# Sport_Analyzer_1_0_1.net
KiCad netlist of a schematic drawn in EAGLE
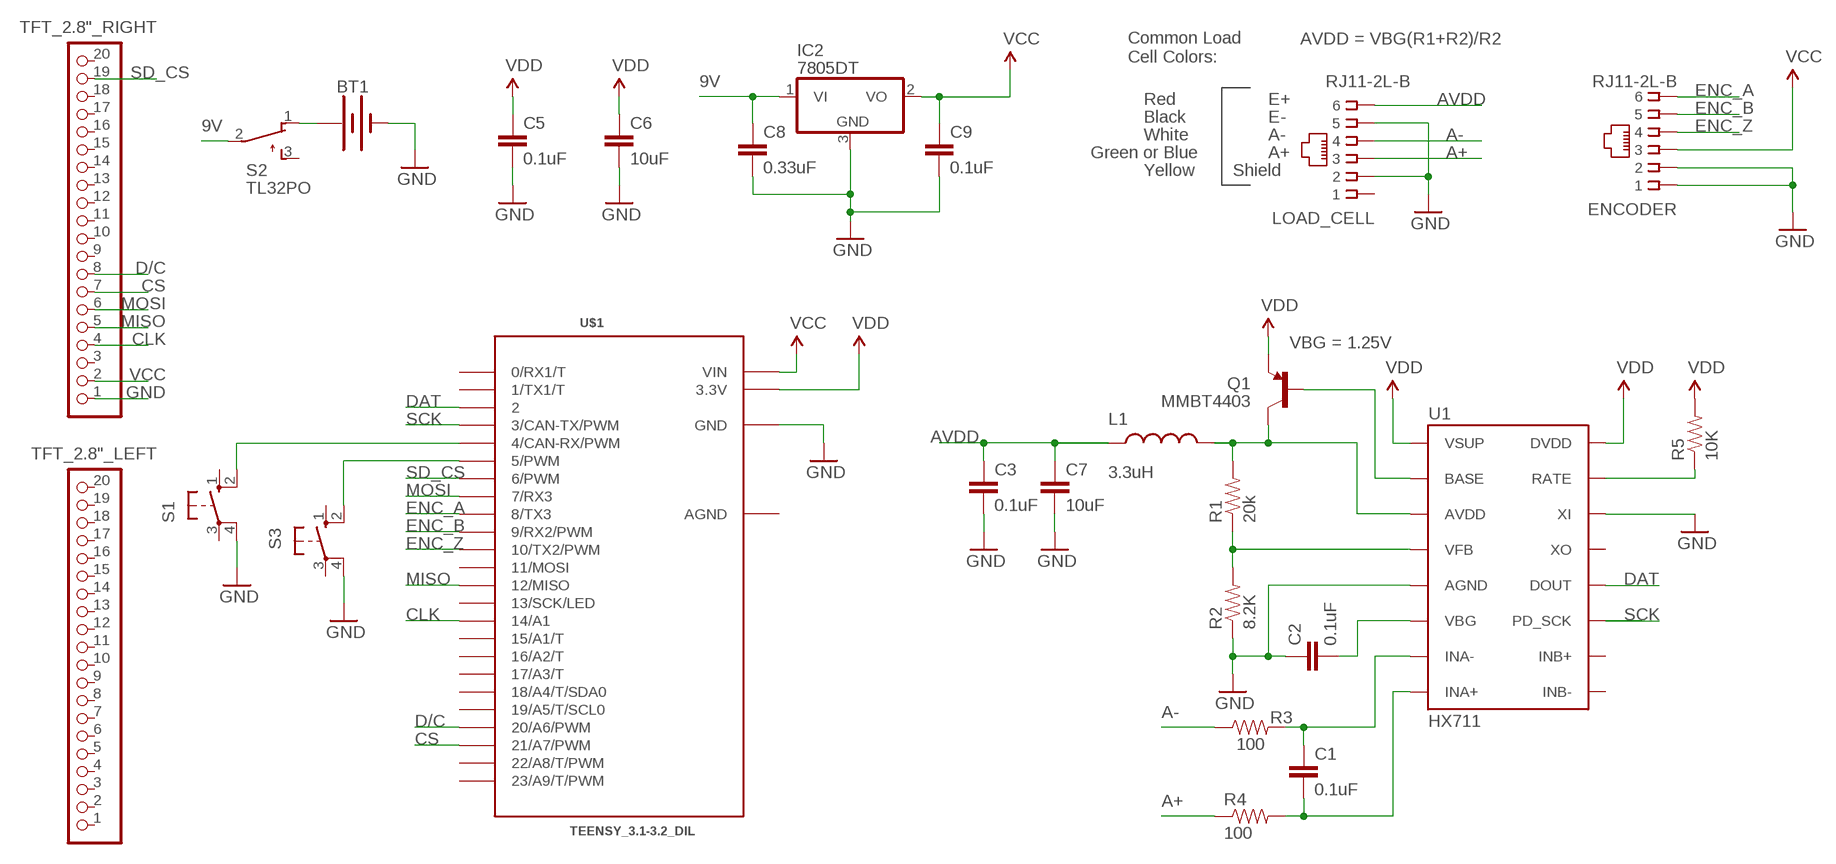
[diagram p0: schematic, sheet 1]

(export (version "E")
  (design (tool "Eeschema 10.0.6"))
  (components
    (comp (ref "BT1")
      (value "BATTERY-9V")
      (footprint "eagle-import:BATTCON_9V")
      (libsource (lib "eagle-import") (part "BATTERY-9V"))
    )
    (comp (ref "C1")
      (value "0.1uF")
      (footprint "eagle-import:0603-CAP")
      (libsource (lib "eagle-import") (part "0.1UF-25V-5%(0603)"))
    )
    (comp (ref "C2")
      (value "0.1uF")
      (footprint "eagle-import:0603-CAP")
      (libsource (lib "eagle-import") (part "0.1UF-25V-5%(0603)"))
    )
    (comp (ref "C3")
      (value "0.1uF")
      (footprint "eagle-import:0603-CAP")
      (libsource (lib "eagle-import") (part "0.1UF-25V-5%(0603)"))
    )
    (comp (ref "C5")
      (value "0.1uF")
      (footprint "eagle-import:0603-CAP")
      (libsource (lib "eagle-import") (part "0.1UF-25V-5%(0603)"))
    )
    (comp (ref "C6")
      (value "10uF")
      (footprint "eagle-import:1210")
      (libsource (lib "eagle-import") (part "10UF50V20%(1210)"))
    )
    (comp (ref "C7")
      (value "10uF")
      (footprint "eagle-import:1210")
      (libsource (lib "eagle-import") (part "10UF50V20%(1210)"))
    )
    (comp (ref "C8")
      (value "0.33uF")
      (footprint "eagle-import:0603-CAP")
      (libsource (lib "eagle-import") (part "0.1UF-25V-5%(0603)"))
    )
    (comp (ref "C9")
      (value "0.1uF")
      (footprint "eagle-import:0603-CAP")
      (libsource (lib "eagle-import") (part "0.1UF-25V-5%(0603)"))
    )
    (comp (ref "ENCODER")
      (value "RJ11-2L-B")
      (footprint "eagle-import:RJ11-NO_SHIELD")
      (fields (field (name "MF") "TYCO ELECTRONICS"))
      (libsource (lib "eagle-import") (part "RJ11-2L-B"))
    )
    (comp (ref "IC2")
      (value "7805DT")
      (footprint "eagle-import:TO252")
      (libsource (lib "eagle-import") (part "78DT05"))
    )
    (comp (ref "L1")
      (value "3.3uH")
      (footprint "eagle-import:0805")
      (libsource (lib "eagle-import") (part "INDUCTOR0805-IND"))
    )
    (comp (ref "LOAD_CELL")
      (value "RJ11-2L-B")
      (footprint "eagle-import:RJ11-NO_SHIELD")
      (fields (field (name "MF") "TYCO ELECTRONICS"))
      (libsource (lib "eagle-import") (part "RJ11-2L-B"))
    )
    (comp (ref "Q1")
      (value "MMBT4403")
      (footprint "eagle-import:SOT23-3")
      (libsource (lib "eagle-import") (part "TRANSISTOR_PNPMMBT4403"))
    )
    (comp (ref "R1")
      (value "20k")
      (footprint "eagle-import:0603-RES")
      (libsource (lib "eagle-import") (part "20KOHM1/10W1%(0603)"))
    )
    (comp (ref "R2")
      (value "8.2K")
      (footprint "eagle-import:0603-RES")
      (libsource (lib "eagle-import") (part "8.2KOHM-1/10W-5%(0603)"))
    )
    (comp (ref "R3")
      (value "100")
      (footprint "eagle-import:0603-RES")
      (libsource (lib "eagle-import") (part "100OHM-1/10W-1%(0603)"))
    )
    (comp (ref "R4")
      (value "100")
      (footprint "eagle-import:0603-RES")
      (libsource (lib "eagle-import") (part "100OHM-1/10W-1%(0603)"))
    )
    (comp (ref "R5")
      (value "10K")
      (footprint "eagle-import:0603-RES")
      (libsource (lib "eagle-import") (part "10KOHM-1/10W-1%(0603)0603"))
    )
    (comp (ref "S1")
      (value "10-XX")
      (footprint "eagle-import:B3F-10XX")
      (fields (field (name "MPN") "B3F-1000"))
      (libsource (lib "eagle-import") (part "10-XX"))
    )
    (comp (ref "S2")
      (value "TL32PO")
      (footprint "eagle-import:TL3XPO")
      (libsource (lib "eagle-import") (part "TL32PO"))
    )
    (comp (ref "S3")
      (value "10-XX")
      (footprint "eagle-import:B3F-10XX")
      (fields (field (name "MPN") "B3F-1000"))
      (libsource (lib "eagle-import") (part "10-XX"))
    )
    (comp (ref "TFT_2.8\"_LEFT")
      (value "PINHD-1X20")
      (footprint "eagle-import:1X20")
      (libsource (lib "eagle-import") (part "PINHD-1X20"))
    )
    (comp (ref "TFT_2.8\"_RIGHT")
      (value "PINHD-1X20")
      (footprint "eagle-import:1X20")
      (libsource (lib "eagle-import") (part "PINHD-1X20"))
    )
    (comp (ref "U$1")
      (value "TEENSY_3.1-3.2_DIL")
      (footprint "eagle-import:TEENSY_3.0-3.2&LC_DIL")
      (libsource (lib "eagle-import") (part "TEENSY_3.1-3.2_DIL"))
    )
    (comp (ref "U1")
      (value "HX711")
      (footprint "eagle-import:SO16")
      (libsource (lib "eagle-import") (part "HX711HX711"))
    )
  )
  (nets
    (net (code "1") (name "/9V") (class "Default")
      (node (ref "C8") (pin "1") (pinfunction "1_1") (pintype "passive"))
      (node (ref "IC2") (pin "1") (pinfunction "VI_1") (pintype "input"))
      (node (ref "S2") (pin "2") (pinfunction "P_2") (pintype "passive"))
    )
    (net (code "2") (name "/A+") (class "Default")
      (node (ref "LOAD_CELL") (pin "3") (pinfunction "3_3") (pintype "passive"))
      (node (ref "R4") (pin "1") (pinfunction "1_1") (pintype "passive"))
    )
    (net (code "3") (name "/A-") (class "Default")
      (node (ref "LOAD_CELL") (pin "4") (pinfunction "4_4") (pintype "passive"))
      (node (ref "R3") (pin "1") (pinfunction "1_1") (pintype "passive"))
    )
    (net (code "4") (name "/AGND") (class "Default")
      (node (ref "U$1") (pin "AGND") (pinfunction "AGND_AGND") (pintype "power_in"))
    )
    (net (code "5") (name "/AVDD") (class "Default")
      (node (ref "C3") (pin "1") (pinfunction "1_1") (pintype "passive"))
      (node (ref "C7") (pin "1") (pinfunction "1_1") (pintype "passive"))
      (node (ref "L1") (pin "1") (pinfunction "1_1") (pintype "passive"))
      (node (ref "LOAD_CELL") (pin "6") (pinfunction "6_6") (pintype "passive"))
    )
    (net (code "6") (name "/CLK") (class "Default")
      (node (ref "TFT_2.8\"_RIGHT") (pin "4") (pinfunction "4_4") (pintype "passive"))
      (node (ref "U$1") (pin "14/A0") (pinfunction "14/A1_14/A0") (pintype "bidirectional"))
    )
    (net (code "7") (name "/CS") (class "Default")
      (node (ref "TFT_2.8\"_RIGHT") (pin "7") (pinfunction "7_7") (pintype "passive"))
      (node (ref "U$1") (pin "21/A7") (pinfunction "21/A7/PWM_21/A7") (pintype "bidirectional"))
    )
    (net (code "8") (name "/DAT") (class "Default")
      (node (ref "U$1") (pin "2") (pinfunction "2_2") (pintype "bidirectional"))
      (node (ref "U1") (pin "12") (pinfunction "DOUT_12") (pintype "bidirectional"))
    )
    (net (code "9") (name "/D{slash}C") (class "Default")
      (node (ref "TFT_2.8\"_RIGHT") (pin "8") (pinfunction "8_8") (pintype "passive"))
      (node (ref "U$1") (pin "20/A6") (pinfunction "20/A6/PWM_20/A6") (pintype "bidirectional"))
    )
    (net (code "10") (name "/ENC_A") (class "Default")
      (node (ref "ENCODER") (pin "6") (pinfunction "6_6") (pintype "passive"))
      (node (ref "U$1") (pin "8") (pinfunction "8/TX3_8") (pintype "bidirectional"))
    )
    (net (code "11") (name "/ENC_B") (class "Default")
      (node (ref "ENCODER") (pin "5") (pinfunction "5_5") (pintype "passive"))
      (node (ref "U$1") (pin "9") (pinfunction "9/RX2/PWM_9") (pintype "bidirectional"))
    )
    (net (code "12") (name "/ENC_Z") (class "Default")
      (node (ref "ENCODER") (pin "4") (pinfunction "4_4") (pintype "passive"))
      (node (ref "U$1") (pin "10") (pinfunction "10/TX2/PWM_10") (pintype "bidirectional"))
    )
    (net (code "13") (name "/MISO") (class "Default")
      (node (ref "TFT_2.8\"_RIGHT") (pin "5") (pinfunction "5_5") (pintype "passive"))
      (node (ref "U$1") (pin "12") (pinfunction "12/MISO_12") (pintype "bidirectional"))
    )
    (net (code "14") (name "/MOSI") (class "Default")
      (node (ref "TFT_2.8\"_RIGHT") (pin "6") (pinfunction "6_6") (pintype "passive"))
      (node (ref "U$1") (pin "7") (pinfunction "7/RX3_7") (pintype "bidirectional"))
    )
    (net (code "15") (name "/SCK") (class "Default")
      (node (ref "U$1") (pin "3") (pinfunction "3/CAN-TX/PWM_3") (pintype "bidirectional"))
      (node (ref "U1") (pin "11") (pinfunction "PD_SCK_11") (pintype "bidirectional"))
    )
    (net (code "16") (name "/SD_CS") (class "Default")
      (node (ref "TFT_2.8\"_RIGHT") (pin "19") (pinfunction "19_19") (pintype "passive"))
      (node (ref "U$1") (pin "6") (pinfunction "6/PWM_6") (pintype "bidirectional"))
    )
    (net (code "17") (name "GND") (class "Default")
      (node (ref "BT1") (pin "-") (pinfunction "-_-") (pintype "power_in"))
      (node (ref "C2") (pin "1") (pinfunction "1_1") (pintype "passive"))
      (node (ref "C3") (pin "2") (pinfunction "2_2") (pintype "passive"))
      (node (ref "C5") (pin "2") (pinfunction "2_2") (pintype "passive"))
      (node (ref "C6") (pin "2") (pinfunction "2_2") (pintype "passive"))
      (node (ref "C7") (pin "2") (pinfunction "2_2") (pintype "passive"))
      (node (ref "C8") (pin "2") (pinfunction "2_2") (pintype "passive"))
      (node (ref "C9") (pin "2") (pinfunction "2_2") (pintype "passive"))
      (node (ref "ENCODER") (pin "1") (pinfunction "1_1") (pintype "passive"))
      (node (ref "ENCODER") (pin "2") (pinfunction "2_2") (pintype "passive"))
      (node (ref "IC2") (pin "3") (pinfunction "GND_3") (pintype "passive"))
      (node (ref "LOAD_CELL") (pin "2") (pinfunction "2_2") (pintype "passive"))
      (node (ref "LOAD_CELL") (pin "5") (pinfunction "5_5") (pintype "passive"))
      (node (ref "R2") (pin "1") (pinfunction "1_1") (pintype "passive"))
      (node (ref "S1") (pin "4") (pinfunction "P1_4") (pintype "passive"))
      (node (ref "S3") (pin "4") (pinfunction "P1_4") (pintype "passive"))
      (node (ref "TFT_2.8\"_RIGHT") (pin "1") (pinfunction "1_1") (pintype "passive"))
      (node (ref "U$1") (pin "GND") (pinfunction "GND_GND") (pintype "power_in"))
      (node (ref "U1") (pin "14") (pinfunction "XI_14") (pintype "bidirectional"))
      (node (ref "U1") (pin "5") (pinfunction "AGND_5") (pintype "bidirectional"))
    )
    (net (code "18") (name "Net-(Q1-B)") (class "Default")
      (node (ref "Q1") (pin "1") (pinfunction "B_1") (pintype "passive"))
      (node (ref "U1") (pin "2") (pinfunction "BASE_2") (pintype "bidirectional"))
    )
    (net (code "19") (name "Net-(Q1-C)") (class "Default")
      (node (ref "L1") (pin "2") (pinfunction "2_2") (pintype "passive"))
      (node (ref "Q1") (pin "3") (pinfunction "C_3") (pintype "passive"))
      (node (ref "R1") (pin "2") (pinfunction "2_2") (pintype "passive"))
      (node (ref "U1") (pin "3") (pinfunction "AVDD_3") (pintype "bidirectional"))
    )
    (net (code "20") (name "Net-(S1-S1)") (class "Default")
      (node (ref "S1") (pin "2") (pinfunction "S1_2") (pintype "passive"))
      (node (ref "U$1") (pin "4") (pinfunction "4/CAN-RX/PWM_4") (pintype "bidirectional"))
    )
    (net (code "21") (name "Net-(S2-O)") (class "Default")
      (node (ref "BT1") (pin "+") (pinfunction "+_+") (pintype "power_in"))
      (node (ref "S2") (pin "1") (pinfunction "O_1") (pintype "passive"))
    )
    (net (code "22") (name "Net-(S3-S1)") (class "Default")
      (node (ref "S3") (pin "2") (pinfunction "S1_2") (pintype "passive"))
      (node (ref "U$1") (pin "5") (pinfunction "5/PWM_5") (pintype "bidirectional"))
    )
    (net (code "23") (name "Net-(U1-INA+)") (class "Default")
      (node (ref "C1") (pin "2") (pinfunction "2_2") (pintype "passive"))
      (node (ref "R4") (pin "2") (pinfunction "2_2") (pintype "passive"))
      (node (ref "U1") (pin "8") (pinfunction "INA+_8") (pintype "bidirectional"))
    )
    (net (code "24") (name "Net-(U1-INA-)") (class "Default")
      (node (ref "C1") (pin "1") (pinfunction "1_1") (pintype "passive"))
      (node (ref "R3") (pin "2") (pinfunction "2_2") (pintype "passive"))
      (node (ref "U1") (pin "7") (pinfunction "INA-_7") (pintype "bidirectional"))
    )
    (net (code "25") (name "Net-(U1-RATE)") (class "Default")
      (node (ref "R5") (pin "1") (pinfunction "1_1") (pintype "passive"))
      (node (ref "U1") (pin "15") (pinfunction "RATE_15") (pintype "bidirectional"))
    )
    (net (code "26") (name "Net-(U1-VBG)") (class "Default")
      (node (ref "C2") (pin "2") (pinfunction "2_2") (pintype "passive"))
      (node (ref "U1") (pin "6") (pinfunction "VBG_6") (pintype "bidirectional"))
    )
    (net (code "27") (name "Net-(U1-VFB)") (class "Default")
      (node (ref "R1") (pin "1") (pinfunction "1_1") (pintype "passive"))
      (node (ref "R2") (pin "2") (pinfunction "2_2") (pintype "passive"))
      (node (ref "U1") (pin "4") (pinfunction "VFB_4") (pintype "bidirectional"))
    )
    (net (code "28") (name "VCC") (class "Default")
      (node (ref "C9") (pin "1") (pinfunction "1_1") (pintype "passive"))
      (node (ref "ENCODER") (pin "3") (pinfunction "3_3") (pintype "passive"))
      (node (ref "IC2") (pin "2") (pinfunction "VO_2") (pintype "passive"))
      (node (ref "TFT_2.8\"_RIGHT") (pin "2") (pinfunction "2_2") (pintype "passive"))
      (node (ref "U$1") (pin "VIN") (pinfunction "VIN_VIN") (pintype "power_in"))
    )
    (net (code "29") (name "VDD") (class "Default")
      (node (ref "C5") (pin "1") (pinfunction "1_1") (pintype "passive"))
      (node (ref "C6") (pin "1") (pinfunction "1_1") (pintype "passive"))
      (node (ref "Q1") (pin "2") (pinfunction "E_2") (pintype "passive"))
      (node (ref "R5") (pin "2") (pinfunction "2_2") (pintype "passive"))
      (node (ref "U$1") (pin "3.3V") (pinfunction "3.3V_3.3V") (pintype "power_in"))
      (node (ref "U1") (pin "1") (pinfunction "VSUP_1") (pintype "bidirectional"))
      (node (ref "U1") (pin "16") (pinfunction "DVDD_16") (pintype "bidirectional"))
    )
    (net (code "30") (name "unconnected-(LOAD_CELL-Pad1)") (class "Default")
      (node (ref "LOAD_CELL") (pin "1") (pinfunction "1_1") (pintype "passive"))
    )
    (net (code "31") (name "unconnected-(S1-P-Pad3)") (class "Default")
      (node (ref "S1") (pin "3") (pinfunction "P_3") (pintype "passive"))
    )
    (net (code "32") (name "unconnected-(S1-S-Pad1)") (class "Default")
      (node (ref "S1") (pin "1") (pinfunction "S_1") (pintype "passive"))
    )
    (net (code "33") (name "unconnected-(S2-S-Pad3)") (class "Default")
      (node (ref "S2") (pin "3") (pinfunction "S_3") (pintype "passive"))
    )
    (net (code "34") (name "unconnected-(S3-P-Pad3)") (class "Default")
      (node (ref "S3") (pin "3") (pinfunction "P_3") (pintype "passive"))
    )
    (net (code "35") (name "unconnected-(S3-S-Pad1)") (class "Default")
      (node (ref "S3") (pin "1") (pinfunction "S_1") (pintype "passive"))
    )
    (net (code "36") (name "unconnected-(TFT_2.8\"_LEFT-Pad1)") (class "Default")
      (node (ref "TFT_2.8\"_LEFT") (pin "1") (pinfunction "1_1") (pintype "passive"))
    )
    (net (code "37") (name "unconnected-(TFT_2.8\"_LEFT-Pad2)") (class "Default")
      (node (ref "TFT_2.8\"_LEFT") (pin "2") (pinfunction "2_2") (pintype "passive"))
    )
    (net (code "38") (name "unconnected-(TFT_2.8\"_LEFT-Pad3)") (class "Default")
      (node (ref "TFT_2.8\"_LEFT") (pin "3") (pinfunction "3_3") (pintype "passive"))
    )
    (net (code "39") (name "unconnected-(TFT_2.8\"_LEFT-Pad4)") (class "Default")
      (node (ref "TFT_2.8\"_LEFT") (pin "4") (pinfunction "4_4") (pintype "passive"))
    )
    (net (code "40") (name "unconnected-(TFT_2.8\"_LEFT-Pad5)") (class "Default")
      (node (ref "TFT_2.8\"_LEFT") (pin "5") (pinfunction "5_5") (pintype "passive"))
    )
    (net (code "41") (name "unconnected-(TFT_2.8\"_LEFT-Pad6)") (class "Default")
      (node (ref "TFT_2.8\"_LEFT") (pin "6") (pinfunction "6_6") (pintype "passive"))
    )
    (net (code "42") (name "unconnected-(TFT_2.8\"_LEFT-Pad7)") (class "Default")
      (node (ref "TFT_2.8\"_LEFT") (pin "7") (pinfunction "7_7") (pintype "passive"))
    )
    (net (code "43") (name "unconnected-(TFT_2.8\"_LEFT-Pad8)") (class "Default")
      (node (ref "TFT_2.8\"_LEFT") (pin "8") (pinfunction "8_8") (pintype "passive"))
    )
    (net (code "44") (name "unconnected-(TFT_2.8\"_LEFT-Pad9)") (class "Default")
      (node (ref "TFT_2.8\"_LEFT") (pin "9") (pinfunction "9_9") (pintype "passive"))
    )
    (net (code "45") (name "unconnected-(TFT_2.8\"_LEFT-Pad10)") (class "Default")
      (node (ref "TFT_2.8\"_LEFT") (pin "10") (pinfunction "10_10") (pintype "passive"))
    )
    (net (code "46") (name "unconnected-(TFT_2.8\"_LEFT-Pad11)") (class "Default")
      (node (ref "TFT_2.8\"_LEFT") (pin "11") (pinfunction "11_11") (pintype "passive"))
    )
    (net (code "47") (name "unconnected-(TFT_2.8\"_LEFT-Pad12)") (class "Default")
      (node (ref "TFT_2.8\"_LEFT") (pin "12") (pinfunction "12_12") (pintype "passive"))
    )
    (net (code "48") (name "unconnected-(TFT_2.8\"_LEFT-Pad13)") (class "Default")
      (node (ref "TFT_2.8\"_LEFT") (pin "13") (pinfunction "13_13") (pintype "passive"))
    )
    (net (code "49") (name "unconnected-(TFT_2.8\"_LEFT-Pad14)") (class "Default")
      (node (ref "TFT_2.8\"_LEFT") (pin "14") (pinfunction "14_14") (pintype "passive"))
    )
    (net (code "50") (name "unconnected-(TFT_2.8\"_LEFT-Pad15)") (class "Default")
      (node (ref "TFT_2.8\"_LEFT") (pin "15") (pinfunction "15_15") (pintype "passive"))
    )
    (net (code "51") (name "unconnected-(TFT_2.8\"_LEFT-Pad16)") (class "Default")
      (node (ref "TFT_2.8\"_LEFT") (pin "16") (pinfunction "16_16") (pintype "passive"))
    )
    (net (code "52") (name "unconnected-(TFT_2.8\"_LEFT-Pad17)") (class "Default")
      (node (ref "TFT_2.8\"_LEFT") (pin "17") (pinfunction "17_17") (pintype "passive"))
    )
    (net (code "53") (name "unconnected-(TFT_2.8\"_LEFT-Pad18)") (class "Default")
      (node (ref "TFT_2.8\"_LEFT") (pin "18") (pinfunction "18_18") (pintype "passive"))
    )
    (net (code "54") (name "unconnected-(TFT_2.8\"_LEFT-Pad19)") (class "Default")
      (node (ref "TFT_2.8\"_LEFT") (pin "19") (pinfunction "19_19") (pintype "passive"))
    )
    (net (code "55") (name "unconnected-(TFT_2.8\"_LEFT-Pad20)") (class "Default")
      (node (ref "TFT_2.8\"_LEFT") (pin "20") (pinfunction "20_20") (pintype "passive"))
    )
    (net (code "56") (name "unconnected-(TFT_2.8\"_RIGHT-Pad3)") (class "Default")
      (node (ref "TFT_2.8\"_RIGHT") (pin "3") (pinfunction "3_3") (pintype "passive"))
    )
    (net (code "57") (name "unconnected-(TFT_2.8\"_RIGHT-Pad9)") (class "Default")
      (node (ref "TFT_2.8\"_RIGHT") (pin "9") (pinfunction "9_9") (pintype "passive"))
    )
    (net (code "58") (name "unconnected-(TFT_2.8\"_RIGHT-Pad10)") (class "Default")
      (node (ref "TFT_2.8\"_RIGHT") (pin "10") (pinfunction "10_10") (pintype "passive"))
    )
    (net (code "59") (name "unconnected-(TFT_2.8\"_RIGHT-Pad11)") (class "Default")
      (node (ref "TFT_2.8\"_RIGHT") (pin "11") (pinfunction "11_11") (pintype "passive"))
    )
    (net (code "60") (name "unconnected-(TFT_2.8\"_RIGHT-Pad12)") (class "Default")
      (node (ref "TFT_2.8\"_RIGHT") (pin "12") (pinfunction "12_12") (pintype "passive"))
    )
    (net (code "61") (name "unconnected-(TFT_2.8\"_RIGHT-Pad13)") (class "Default")
      (node (ref "TFT_2.8\"_RIGHT") (pin "13") (pinfunction "13_13") (pintype "passive"))
    )
    (net (code "62") (name "unconnected-(TFT_2.8\"_RIGHT-Pad14)") (class "Default")
      (node (ref "TFT_2.8\"_RIGHT") (pin "14") (pinfunction "14_14") (pintype "passive"))
    )
    (net (code "63") (name "unconnected-(TFT_2.8\"_RIGHT-Pad15)") (class "Default")
      (node (ref "TFT_2.8\"_RIGHT") (pin "15") (pinfunction "15_15") (pintype "passive"))
    )
    (net (code "64") (name "unconnected-(TFT_2.8\"_RIGHT-Pad16)") (class "Default")
      (node (ref "TFT_2.8\"_RIGHT") (pin "16") (pinfunction "16_16") (pintype "passive"))
    )
    (net (code "65") (name "unconnected-(TFT_2.8\"_RIGHT-Pad17)") (class "Default")
      (node (ref "TFT_2.8\"_RIGHT") (pin "17") (pinfunction "17_17") (pintype "passive"))
    )
    (net (code "66") (name "unconnected-(TFT_2.8\"_RIGHT-Pad18)") (class "Default")
      (node (ref "TFT_2.8\"_RIGHT") (pin "18") (pinfunction "18_18") (pintype "passive"))
    )
    (net (code "67") (name "unconnected-(TFT_2.8\"_RIGHT-Pad20)") (class "Default")
      (node (ref "TFT_2.8\"_RIGHT") (pin "20") (pinfunction "20_20") (pintype "passive"))
    )
    (net (code "68") (name "unconnected-(U$1-0{slash}RX1{slash}T-Pad0)") (class "Default")
      (node (ref "U$1") (pin "0") (pinfunction "0/RX1/T_0") (pintype "bidirectional"))
    )
    (net (code "69") (name "unconnected-(U$1-1{slash}TX1{slash}T-Pad1)") (class "Default")
      (node (ref "U$1") (pin "1") (pinfunction "1/TX1/T_1") (pintype "bidirectional"))
    )
    (net (code "70") (name "unconnected-(U$1-11{slash}MOSI-Pad11)") (class "Default")
      (node (ref "U$1") (pin "11") (pinfunction "11/MOSI_11") (pintype "bidirectional"))
    )
    (net (code "71") (name "unconnected-(U$1-13{slash}SCK{slash}LED-Pad13)") (class "Default")
      (node (ref "U$1") (pin "13") (pinfunction "13/SCK/LED_13") (pintype "bidirectional"))
    )
    (net (code "72") (name "unconnected-(U$1-15{slash}A1{slash}T-Pad15{slash}A1)") (class "Default")
      (node (ref "U$1") (pin "15/A1") (pinfunction "15/A1/T_15/A1") (pintype "bidirectional"))
    )
    (net (code "73") (name "unconnected-(U$1-16{slash}A2{slash}T-Pad16{slash}A2)") (class "Default")
      (node (ref "U$1") (pin "16/A2") (pinfunction "16/A2/T_16/A2") (pintype "bidirectional"))
    )
    (net (code "74") (name "unconnected-(U$1-17{slash}A3{slash}T-Pad17{slash}A3)") (class "Default")
      (node (ref "U$1") (pin "17/A3") (pinfunction "17/A3/T_17/A3") (pintype "bidirectional"))
    )
    (net (code "75") (name "unconnected-(U$1-18{slash}A4{slash}T{slash}SDA0-Pad18{slash}A4)") (class "Default")
      (node (ref "U$1") (pin "18/A4") (pinfunction "18/A4/T/SDA0_18/A4") (pintype "bidirectional"))
    )
    (net (code "76") (name "unconnected-(U$1-19{slash}A5{slash}T{slash}SCL0-Pad19{slash}A5)") (class "Default")
      (node (ref "U$1") (pin "19/A5") (pinfunction "19/A5/T/SCL0_19/A5") (pintype "bidirectional"))
    )
    (net (code "77") (name "unconnected-(U$1-22{slash}A8{slash}T{slash}PWM-Pad22{slash}A8)") (class "Default")
      (node (ref "U$1") (pin "22/A8") (pinfunction "22/A8/T/PWM_22/A8") (pintype "bidirectional"))
    )
    (net (code "78") (name "unconnected-(U$1-23{slash}A9{slash}T{slash}PWM-Pad23{slash}A9)") (class "Default")
      (node (ref "U$1") (pin "23/A9") (pinfunction "23/A9/T/PWM_23/A9") (pintype "bidirectional"))
    )
    (net (code "79") (name "unconnected-(U1-INB+-Pad10)") (class "Default")
      (node (ref "U1") (pin "10") (pinfunction "INB+_10") (pintype "bidirectional"))
    )
    (net (code "80") (name "unconnected-(U1-INB--Pad9)") (class "Default")
      (node (ref "U1") (pin "9") (pinfunction "INB-_9") (pintype "bidirectional"))
    )
    (net (code "81") (name "unconnected-(U1-XO-Pad13)") (class "Default")
      (node (ref "U1") (pin "13") (pinfunction "XO_13") (pintype "bidirectional"))
    )
  )
)
